# Drive.net
KiCad netlist of a schematic drawn in Altium Designer
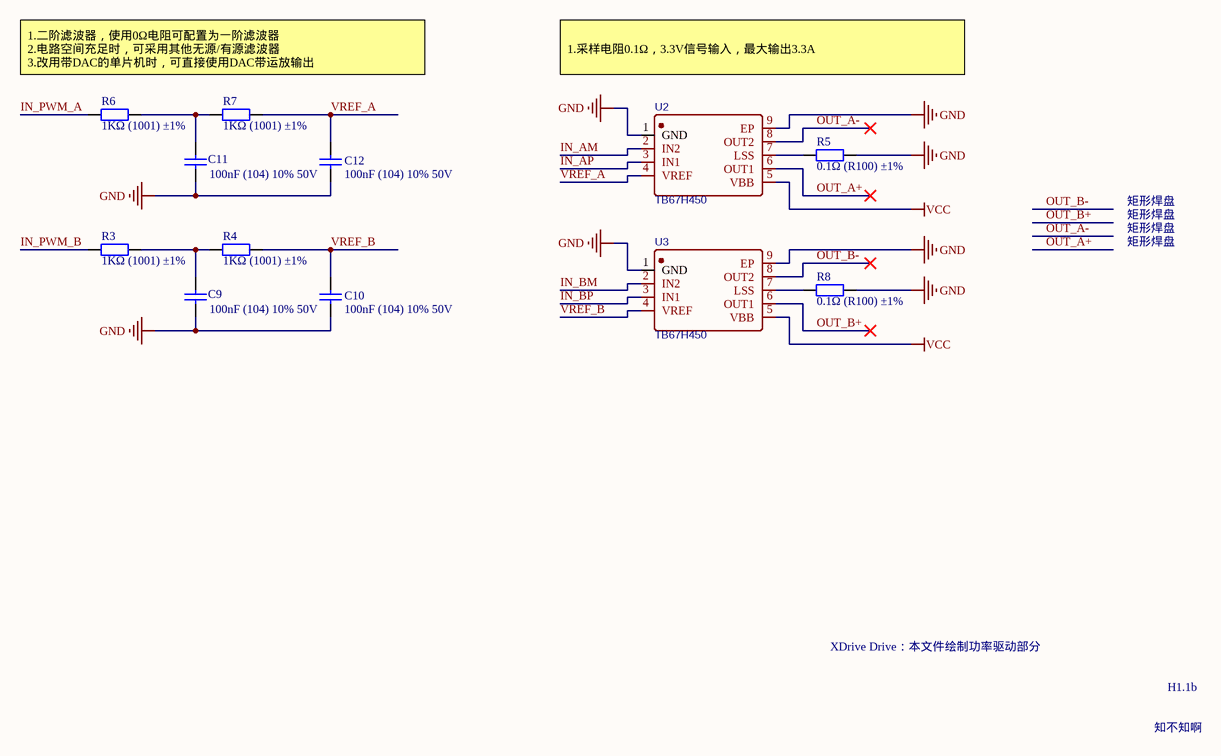
[diagram p0: Drive.SchDoc]

(export (version "E")
  (design (tool "Eeschema 10.0.6"))
  (components
    (comp (ref "C9")
      (value "100nF (104) 10% 50V")
      (footprint "0603_C")
      (description "贴片电容")
      (libsource (lib "Miscellaneous Devices LC") (part "0603 100nF (104) 10% 50V"))
    )
    (comp (ref "C10")
      (value "100nF (104) 10% 50V")
      (footprint "0603_C")
      (description "贴片电容")
      (libsource (lib "Miscellaneous Devices LC") (part "0603 100nF (104) 10% 50V"))
    )
    (comp (ref "C11")
      (value "100nF (104) 10% 50V")
      (footprint "0603_C")
      (description "贴片电容")
      (libsource (lib "Miscellaneous Devices LC") (part "0603 100nF (104) 10% 50V"))
    )
    (comp (ref "C12")
      (value "100nF (104) 10% 50V")
      (footprint "0603_C")
      (description "贴片电容")
      (libsource (lib "Miscellaneous Devices LC") (part "0603 100nF (104) 10% 50V"))
    )
    (comp (ref "R3")
      (value "1KΩ (1001) ±1%")
      (footprint "0603_R")
      (description "贴片电阻")
      (libsource (lib "Miscellaneous Devices LC") (part "0603 1KΩ (1001) 1%"))
    )
    (comp (ref "R4")
      (value "1KΩ (1001) ±1%")
      (footprint "0603_R")
      (description "贴片电阻")
      (libsource (lib "Miscellaneous Devices LC") (part "0603 1KΩ (1001) 1%"))
    )
    (comp (ref "R5")
      (value "0.1Ω (R100) ±1%")
      (footprint "1206_R")
      (description "贴片电阻")
      (libsource (lib "Miscellaneous Devices LC") (part "1206 0.1Ω (R100) 1%"))
    )
    (comp (ref "R6")
      (value "1KΩ (1001) ±1%")
      (footprint "0603_R")
      (description "贴片电阻")
      (libsource (lib "Miscellaneous Devices LC") (part "0603 1KΩ (1001) 1%"))
    )
    (comp (ref "R7")
      (value "1KΩ (1001) ±1%")
      (footprint "0603_R")
      (description "贴片电阻")
      (libsource (lib "Miscellaneous Devices LC") (part "0603 1KΩ (1001) 1%"))
    )
    (comp (ref "R8")
      (value "0.1Ω (R100) ±1%")
      (footprint "1206_R")
      (description "贴片电阻")
      (libsource (lib "Miscellaneous Devices LC") (part "1206 0.1Ω (R100) 1%"))
    )
    (comp (ref "U2")
      (value "TB67H450")
      (footprint "SOIC-8_EP_150MIL")
      (description "直流电机驱动器")
      (fields
        (field (name "BOM_MANUFACTURER PART") "A4950ELJTR-T")
        (field (name "BOM_SUPPLIER PART") "C82404")
      )
      (libsource (lib "ALLGRO-电机驱动") (part "A4950ELJTR-T"))
    )
    (comp (ref "U3")
      (value "TB67H450")
      (footprint "SOIC-8_EP_150MIL")
      (description "直流电机驱动器")
      (fields
        (field (name "BOM_MANUFACTURER PART") "A4950ELJTR-T")
        (field (name "BOM_SUPPLIER PART") "C82404")
      )
      (libsource (lib "ALLGRO-电机驱动") (part "A4950ELJTR-T"))
    )
  )
  (nets
    (net (code "1") (name "/IN_AM") (class "Default")
      (node (ref "U2") (pin "2") (pinfunction "IN2_2") (pintype "passive"))
    )
    (net (code "2") (name "/IN_AP") (class "Default")
      (node (ref "U2") (pin "3") (pinfunction "IN1_3") (pintype "passive"))
    )
    (net (code "3") (name "/IN_BM") (class "Default")
      (node (ref "U3") (pin "2") (pinfunction "IN2_2") (pintype "passive"))
    )
    (net (code "4") (name "/IN_BP") (class "Default")
      (node (ref "U3") (pin "3") (pinfunction "IN1_3") (pintype "passive"))
    )
    (net (code "5") (name "/IN_PWM_A") (class "Default")
      (node (ref "R6") (pin "1") (pinfunction "1_1") (pintype "passive"))
    )
    (net (code "6") (name "/IN_PWM_B") (class "Default")
      (node (ref "R3") (pin "1") (pinfunction "1_1") (pintype "passive"))
    )
    (net (code "7") (name "/OUT_A+") (class "Default")
      (node (ref "U2") (pin "6") (pinfunction "OUT1_6") (pintype "passive+no_connect"))
    )
    (net (code "8") (name "/OUT_A-") (class "Default")
      (node (ref "U2") (pin "8") (pinfunction "OUT2_8") (pintype "passive+no_connect"))
    )
    (net (code "9") (name "/OUT_B+") (class "Default")
      (node (ref "U3") (pin "6") (pinfunction "OUT1_6") (pintype "passive"))
    )
    (net (code "10") (name "/OUT_B-") (class "Default")
      (node (ref "U3") (pin "8") (pinfunction "OUT2_8") (pintype "passive"))
    )
    (net (code "11") (name "/VREF_A") (class "Default")
      (node (ref "C12") (pin "2") (pinfunction "2_2") (pintype "passive"))
      (node (ref "R7") (pin "2") (pinfunction "2_2") (pintype "passive"))
      (node (ref "U2") (pin "4") (pinfunction "VREF_4") (pintype "passive"))
    )
    (net (code "12") (name "/VREF_B") (class "Default")
      (node (ref "C10") (pin "2") (pinfunction "2_2") (pintype "passive"))
      (node (ref "R4") (pin "2") (pinfunction "2_2") (pintype "passive"))
      (node (ref "U3") (pin "4") (pinfunction "VREF_4") (pintype "passive"))
    )
    (net (code "13") (name "GND") (class "Default")
      (node (ref "C10") (pin "1") (pinfunction "1_1") (pintype "passive"))
      (node (ref "C11") (pin "1") (pinfunction "1_1") (pintype "passive"))
      (node (ref "C12") (pin "1") (pinfunction "1_1") (pintype "passive"))
      (node (ref "C9") (pin "1") (pinfunction "1_1") (pintype "passive"))
      (node (ref "R5") (pin "2") (pinfunction "2_2") (pintype "passive"))
      (node (ref "R8") (pin "2") (pinfunction "2_2") (pintype "passive"))
      (node (ref "U2") (pin "1") (pinfunction "GND_1") (pintype "passive"))
      (node (ref "U2") (pin "9") (pinfunction "EP_9") (pintype "passive"))
      (node (ref "U3") (pin "1") (pinfunction "GND_1") (pintype "passive"))
      (node (ref "U3") (pin "9") (pinfunction "EP_9") (pintype "passive"))
    )
    (net (code "14") (name "Net-(C9-Pad2)") (class "Default")
      (node (ref "C9") (pin "2") (pinfunction "2_2") (pintype "passive"))
      (node (ref "R3") (pin "2") (pinfunction "2_2") (pintype "passive"))
      (node (ref "R4") (pin "1") (pinfunction "1_1") (pintype "passive"))
    )
    (net (code "15") (name "Net-(C11-Pad2)") (class "Default")
      (node (ref "C11") (pin "2") (pinfunction "2_2") (pintype "passive"))
      (node (ref "R6") (pin "2") (pinfunction "2_2") (pintype "passive"))
      (node (ref "R7") (pin "1") (pinfunction "1_1") (pintype "passive"))
    )
    (net (code "16") (name "Net-(U2-LSS)") (class "Default")
      (node (ref "R5") (pin "1") (pinfunction "1_1") (pintype "passive"))
      (node (ref "U2") (pin "7") (pinfunction "LSS_7") (pintype "passive"))
    )
    (net (code "17") (name "Net-(U3-LSS)") (class "Default")
      (node (ref "R8") (pin "1") (pinfunction "1_1") (pintype "passive"))
      (node (ref "U3") (pin "7") (pinfunction "LSS_7") (pintype "passive"))
    )
    (net (code "18") (name "VCC") (class "Default")
      (node (ref "U2") (pin "5") (pinfunction "VBB_5") (pintype "passive"))
      (node (ref "U3") (pin "5") (pinfunction "VBB_5") (pintype "passive"))
    )
  )
)
